# 04-ANDStatusLed.net
KiCad netlist of a schematic drawn in Altium Designer
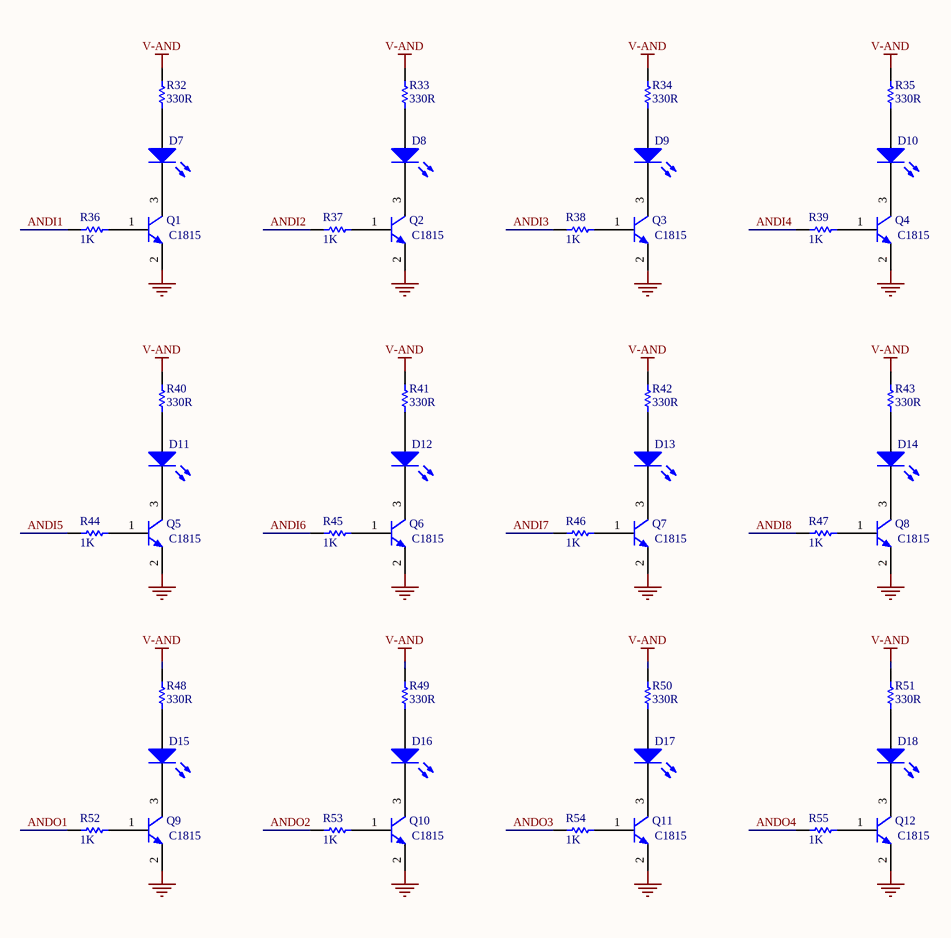
[diagram p0: 04-ANDStatusLed.SchDoc]

(export (version "E")
  (design (tool "Eeschema 10.0.6"))
  (components
    (comp (ref "D7")
      (value "LED")
      (footprint "LED-3528")
      (description "Typical RED, GREEN, YELLOW, AMBER GaAs LED")
      (fields (field (name "PUBLISHER") "Altium Limited"))
      (libsource (lib "Miscellaneous Devices") (part "LED2"))
    )
    (comp (ref "D8")
      (value "LED")
      (footprint "LED-3528")
      (description "Typical RED, GREEN, YELLOW, AMBER GaAs LED")
      (fields (field (name "PUBLISHER") "Altium Limited"))
      (libsource (lib "Miscellaneous Devices") (part "LED2"))
    )
    (comp (ref "D9")
      (value "LED")
      (footprint "LED-3528")
      (description "Typical RED, GREEN, YELLOW, AMBER GaAs LED")
      (fields (field (name "PUBLISHER") "Altium Limited"))
      (libsource (lib "Miscellaneous Devices") (part "LED2"))
    )
    (comp (ref "D10")
      (value "LED")
      (footprint "LED-3528")
      (description "Typical RED, GREEN, YELLOW, AMBER GaAs LED")
      (fields (field (name "PUBLISHER") "Altium Limited"))
      (libsource (lib "Miscellaneous Devices") (part "LED2"))
    )
    (comp (ref "D11")
      (value "LED")
      (footprint "LED-3528")
      (description "Typical RED, GREEN, YELLOW, AMBER GaAs LED")
      (fields (field (name "PUBLISHER") "Altium Limited"))
      (libsource (lib "Miscellaneous Devices") (part "LED2"))
    )
    (comp (ref "D12")
      (value "LED")
      (footprint "LED-3528")
      (description "Typical RED, GREEN, YELLOW, AMBER GaAs LED")
      (fields (field (name "PUBLISHER") "Altium Limited"))
      (libsource (lib "Miscellaneous Devices") (part "LED2"))
    )
    (comp (ref "D13")
      (value "LED")
      (footprint "LED-3528")
      (description "Typical RED, GREEN, YELLOW, AMBER GaAs LED")
      (fields (field (name "PUBLISHER") "Altium Limited"))
      (libsource (lib "Miscellaneous Devices") (part "LED2"))
    )
    (comp (ref "D14")
      (value "LED")
      (footprint "LED-3528")
      (description "Typical RED, GREEN, YELLOW, AMBER GaAs LED")
      (fields (field (name "PUBLISHER") "Altium Limited"))
      (libsource (lib "Miscellaneous Devices") (part "LED2"))
    )
    (comp (ref "D15")
      (value "LED")
      (footprint "LED-3528")
      (description "Typical RED, GREEN, YELLOW, AMBER GaAs LED")
      (fields (field (name "PUBLISHER") "Altium Limited"))
      (libsource (lib "Miscellaneous Devices") (part "LED2"))
    )
    (comp (ref "D16")
      (value "LED")
      (footprint "LED-3528")
      (description "Typical RED, GREEN, YELLOW, AMBER GaAs LED")
      (fields (field (name "PUBLISHER") "Altium Limited"))
      (libsource (lib "Miscellaneous Devices") (part "LED2"))
    )
    (comp (ref "D17")
      (value "LED")
      (footprint "LED-3528")
      (description "Typical RED, GREEN, YELLOW, AMBER GaAs LED")
      (fields (field (name "PUBLISHER") "Altium Limited"))
      (libsource (lib "Miscellaneous Devices") (part "LED2"))
    )
    (comp (ref "D18")
      (value "LED")
      (footprint "LED-3528")
      (description "Typical RED, GREEN, YELLOW, AMBER GaAs LED")
      (fields (field (name "PUBLISHER") "Altium Limited"))
      (libsource (lib "Miscellaneous Devices") (part "LED2"))
    )
    (comp (ref "Q1")
      (value "C1815")
      (footprint "SOT23-321")
      (description "NPN Bipolar Transistor")
      (fields (field (name "Comment") "C1815-SMD"))
      (libsource (lib "Miscellaneous Devices") (part "NPN"))
    )
    (comp (ref "Q2")
      (value "C1815")
      (footprint "SOT23-321")
      (description "NPN Bipolar Transistor")
      (fields (field (name "Comment") "C1815-SMD"))
      (libsource (lib "Miscellaneous Devices") (part "NPN"))
    )
    (comp (ref "Q3")
      (value "C1815")
      (footprint "SOT23-321")
      (description "NPN Bipolar Transistor")
      (fields (field (name "Comment") "C1815-SMD"))
      (libsource (lib "Miscellaneous Devices") (part "NPN"))
    )
    (comp (ref "Q4")
      (value "C1815")
      (footprint "SOT23-321")
      (description "NPN Bipolar Transistor")
      (fields (field (name "Comment") "C1815-SMD"))
      (libsource (lib "Miscellaneous Devices") (part "NPN"))
    )
    (comp (ref "Q5")
      (value "C1815")
      (footprint "SOT23-321")
      (description "NPN Bipolar Transistor")
      (fields (field (name "Comment") "C1815-SMD"))
      (libsource (lib "Miscellaneous Devices") (part "NPN"))
    )
    (comp (ref "Q6")
      (value "C1815")
      (footprint "SOT23-321")
      (description "NPN Bipolar Transistor")
      (fields (field (name "Comment") "C1815-SMD"))
      (libsource (lib "Miscellaneous Devices") (part "NPN"))
    )
    (comp (ref "Q7")
      (value "C1815")
      (footprint "SOT23-321")
      (description "NPN Bipolar Transistor")
      (fields (field (name "Comment") "C1815-SMD"))
      (libsource (lib "Miscellaneous Devices") (part "NPN"))
    )
    (comp (ref "Q8")
      (value "C1815")
      (footprint "SOT23-321")
      (description "NPN Bipolar Transistor")
      (fields (field (name "Comment") "C1815-SMD"))
      (libsource (lib "Miscellaneous Devices") (part "NPN"))
    )
    (comp (ref "Q9")
      (value "C1815")
      (footprint "SOT23-321")
      (description "NPN Bipolar Transistor")
      (fields (field (name "Comment") "C1815-SMD"))
      (libsource (lib "Miscellaneous Devices") (part "NPN"))
    )
    (comp (ref "Q10")
      (value "C1815")
      (footprint "SOT23-321")
      (description "NPN Bipolar Transistor")
      (fields (field (name "Comment") "C1815-SMD"))
      (libsource (lib "Miscellaneous Devices") (part "NPN"))
    )
    (comp (ref "Q11")
      (value "C1815")
      (footprint "SOT23-321")
      (description "NPN Bipolar Transistor")
      (fields (field (name "Comment") "C1815-SMD"))
      (libsource (lib "Miscellaneous Devices") (part "NPN"))
    )
    (comp (ref "Q12")
      (value "C1815")
      (footprint "SOT23-321")
      (description "NPN Bipolar Transistor")
      (fields (field (name "Comment") "C1815-SMD"))
      (libsource (lib "Miscellaneous Devices") (part "NPN"))
    )
    (comp (ref "R32")
      (value "330R")
      (footprint "R-0805")
      (description "Resistor")
      (fields (field (name "PUBLISHER") "Altium Limited"))
      (libsource (lib "Miscellaneous Devices") (part "Res1"))
    )
    (comp (ref "R33")
      (value "330R")
      (footprint "R-0805")
      (description "Resistor")
      (fields (field (name "PUBLISHER") "Altium Limited"))
      (libsource (lib "Miscellaneous Devices") (part "Res1"))
    )
    (comp (ref "R34")
      (value "330R")
      (footprint "R-0805")
      (description "Resistor")
      (fields (field (name "PUBLISHER") "Altium Limited"))
      (libsource (lib "Miscellaneous Devices") (part "Res1"))
    )
    (comp (ref "R35")
      (value "330R")
      (footprint "R-0805")
      (description "Resistor")
      (fields (field (name "PUBLISHER") "Altium Limited"))
      (libsource (lib "Miscellaneous Devices") (part "Res1"))
    )
    (comp (ref "R36")
      (value "1K")
      (footprint "R-0805")
      (description "Resistor")
      (fields (field (name "PUBLISHER") "Altium Limited"))
      (libsource (lib "Miscellaneous Devices") (part "Res1"))
    )
    (comp (ref "R37")
      (value "1K")
      (footprint "R-0805")
      (description "Resistor")
      (fields (field (name "PUBLISHER") "Altium Limited"))
      (libsource (lib "Miscellaneous Devices") (part "Res1"))
    )
    (comp (ref "R38")
      (value "1K")
      (footprint "R-0805")
      (description "Resistor")
      (fields (field (name "PUBLISHER") "Altium Limited"))
      (libsource (lib "Miscellaneous Devices") (part "Res1"))
    )
    (comp (ref "R39")
      (value "1K")
      (footprint "R-0805")
      (description "Resistor")
      (fields (field (name "PUBLISHER") "Altium Limited"))
      (libsource (lib "Miscellaneous Devices") (part "Res1"))
    )
    (comp (ref "R40")
      (value "330R")
      (footprint "R-0805")
      (description "Resistor")
      (fields (field (name "PUBLISHER") "Altium Limited"))
      (libsource (lib "Miscellaneous Devices") (part "Res1"))
    )
    (comp (ref "R41")
      (value "330R")
      (footprint "R-0805")
      (description "Resistor")
      (fields (field (name "PUBLISHER") "Altium Limited"))
      (libsource (lib "Miscellaneous Devices") (part "Res1"))
    )
    (comp (ref "R42")
      (value "330R")
      (footprint "R-0805")
      (description "Resistor")
      (fields (field (name "PUBLISHER") "Altium Limited"))
      (libsource (lib "Miscellaneous Devices") (part "Res1"))
    )
    (comp (ref "R43")
      (value "330R")
      (footprint "R-0805")
      (description "Resistor")
      (fields (field (name "PUBLISHER") "Altium Limited"))
      (libsource (lib "Miscellaneous Devices") (part "Res1"))
    )
    (comp (ref "R44")
      (value "1K")
      (footprint "R-0805")
      (description "Resistor")
      (fields (field (name "PUBLISHER") "Altium Limited"))
      (libsource (lib "Miscellaneous Devices") (part "Res1"))
    )
    (comp (ref "R45")
      (value "1K")
      (footprint "R-0805")
      (description "Resistor")
      (fields (field (name "PUBLISHER") "Altium Limited"))
      (libsource (lib "Miscellaneous Devices") (part "Res1"))
    )
    (comp (ref "R46")
      (value "1K")
      (footprint "R-0805")
      (description "Resistor")
      (fields (field (name "PUBLISHER") "Altium Limited"))
      (libsource (lib "Miscellaneous Devices") (part "Res1"))
    )
    (comp (ref "R47")
      (value "1K")
      (footprint "R-0805")
      (description "Resistor")
      (fields (field (name "PUBLISHER") "Altium Limited"))
      (libsource (lib "Miscellaneous Devices") (part "Res1"))
    )
    (comp (ref "R48")
      (value "330R")
      (footprint "R-0805")
      (description "Resistor")
      (fields (field (name "PUBLISHER") "Altium Limited"))
      (libsource (lib "Miscellaneous Devices") (part "Res1"))
    )
    (comp (ref "R49")
      (value "330R")
      (footprint "R-0805")
      (description "Resistor")
      (fields (field (name "PUBLISHER") "Altium Limited"))
      (libsource (lib "Miscellaneous Devices") (part "Res1"))
    )
    (comp (ref "R50")
      (value "330R")
      (footprint "R-0805")
      (description "Resistor")
      (fields (field (name "PUBLISHER") "Altium Limited"))
      (libsource (lib "Miscellaneous Devices") (part "Res1"))
    )
    (comp (ref "R51")
      (value "330R")
      (footprint "R-0805")
      (description "Resistor")
      (fields (field (name "PUBLISHER") "Altium Limited"))
      (libsource (lib "Miscellaneous Devices") (part "Res1"))
    )
    (comp (ref "R52")
      (value "1K")
      (footprint "R-0805")
      (description "Resistor")
      (fields (field (name "PUBLISHER") "Altium Limited"))
      (libsource (lib "Miscellaneous Devices") (part "Res1"))
    )
    (comp (ref "R53")
      (value "1K")
      (footprint "R-0805")
      (description "Resistor")
      (fields (field (name "PUBLISHER") "Altium Limited"))
      (libsource (lib "Miscellaneous Devices") (part "Res1"))
    )
    (comp (ref "R54")
      (value "1K")
      (footprint "R-0805")
      (description "Resistor")
      (fields (field (name "PUBLISHER") "Altium Limited"))
      (libsource (lib "Miscellaneous Devices") (part "Res1"))
    )
    (comp (ref "R55")
      (value "1K")
      (footprint "R-0805")
      (description "Resistor")
      (fields (field (name "PUBLISHER") "Altium Limited"))
      (libsource (lib "Miscellaneous Devices") (part "Res1"))
    )
  )
  (nets
    (net (code "1") (name "/ANDI1") (class "Default")
      (node (ref "R36") (pin "2") (pinfunction "2_2") (pintype "passive"))
    )
    (net (code "2") (name "/ANDI2") (class "Default")
      (node (ref "R37") (pin "2") (pinfunction "2_2") (pintype "passive"))
    )
    (net (code "3") (name "/ANDI3") (class "Default")
      (node (ref "R38") (pin "2") (pinfunction "2_2") (pintype "passive"))
    )
    (net (code "4") (name "/ANDI4") (class "Default")
      (node (ref "R39") (pin "2") (pinfunction "2_2") (pintype "passive"))
    )
    (net (code "5") (name "/ANDI5") (class "Default")
      (node (ref "R44") (pin "2") (pinfunction "2_2") (pintype "passive"))
    )
    (net (code "6") (name "/ANDI6") (class "Default")
      (node (ref "R45") (pin "2") (pinfunction "2_2") (pintype "passive"))
    )
    (net (code "7") (name "/ANDI7") (class "Default")
      (node (ref "R46") (pin "2") (pinfunction "2_2") (pintype "passive"))
    )
    (net (code "8") (name "/ANDI8") (class "Default")
      (node (ref "R47") (pin "2") (pinfunction "2_2") (pintype "passive"))
    )
    (net (code "9") (name "/ANDO1") (class "Default")
      (node (ref "R52") (pin "2") (pinfunction "2_2") (pintype "passive"))
    )
    (net (code "10") (name "/ANDO2") (class "Default")
      (node (ref "R53") (pin "2") (pinfunction "2_2") (pintype "passive"))
    )
    (net (code "11") (name "/ANDO3") (class "Default")
      (node (ref "R54") (pin "2") (pinfunction "2_2") (pintype "passive"))
    )
    (net (code "12") (name "/ANDO4") (class "Default")
      (node (ref "R55") (pin "2") (pinfunction "2_2") (pintype "passive"))
    )
    (net (code "13") (name "GND") (class "Default")
      (node (ref "Q1") (pin "2") (pinfunction "E_2") (pintype "passive"))
      (node (ref "Q10") (pin "2") (pinfunction "E_2") (pintype "passive"))
      (node (ref "Q11") (pin "2") (pinfunction "E_2") (pintype "passive"))
      (node (ref "Q12") (pin "2") (pinfunction "E_2") (pintype "passive"))
      (node (ref "Q2") (pin "2") (pinfunction "E_2") (pintype "passive"))
      (node (ref "Q3") (pin "2") (pinfunction "E_2") (pintype "passive"))
      (node (ref "Q4") (pin "2") (pinfunction "E_2") (pintype "passive"))
      (node (ref "Q5") (pin "2") (pinfunction "E_2") (pintype "passive"))
      (node (ref "Q6") (pin "2") (pinfunction "E_2") (pintype "passive"))
      (node (ref "Q7") (pin "2") (pinfunction "E_2") (pintype "passive"))
      (node (ref "Q8") (pin "2") (pinfunction "E_2") (pintype "passive"))
      (node (ref "Q9") (pin "2") (pinfunction "E_2") (pintype "passive"))
    )
    (net (code "14") (name "Net-(D7-A)") (class "Default")
      (node (ref "D7") (pin "1") (pinfunction "A_1") (pintype "passive"))
      (node (ref "R32") (pin "1") (pinfunction "1_1") (pintype "passive"))
    )
    (net (code "15") (name "Net-(D7-K)") (class "Default")
      (node (ref "D7") (pin "2") (pinfunction "K_2") (pintype "passive"))
      (node (ref "Q1") (pin "3") (pinfunction "C_3") (pintype "passive"))
    )
    (net (code "16") (name "Net-(D8-A)") (class "Default")
      (node (ref "D8") (pin "1") (pinfunction "A_1") (pintype "passive"))
      (node (ref "R33") (pin "1") (pinfunction "1_1") (pintype "passive"))
    )
    (net (code "17") (name "Net-(D8-K)") (class "Default")
      (node (ref "D8") (pin "2") (pinfunction "K_2") (pintype "passive"))
      (node (ref "Q2") (pin "3") (pinfunction "C_3") (pintype "passive"))
    )
    (net (code "18") (name "Net-(D9-A)") (class "Default")
      (node (ref "D9") (pin "1") (pinfunction "A_1") (pintype "passive"))
      (node (ref "R34") (pin "1") (pinfunction "1_1") (pintype "passive"))
    )
    (net (code "19") (name "Net-(D9-K)") (class "Default")
      (node (ref "D9") (pin "2") (pinfunction "K_2") (pintype "passive"))
      (node (ref "Q3") (pin "3") (pinfunction "C_3") (pintype "passive"))
    )
    (net (code "20") (name "Net-(D10-A)") (class "Default")
      (node (ref "D10") (pin "1") (pinfunction "A_1") (pintype "passive"))
      (node (ref "R35") (pin "1") (pinfunction "1_1") (pintype "passive"))
    )
    (net (code "21") (name "Net-(D10-K)") (class "Default")
      (node (ref "D10") (pin "2") (pinfunction "K_2") (pintype "passive"))
      (node (ref "Q4") (pin "3") (pinfunction "C_3") (pintype "passive"))
    )
    (net (code "22") (name "Net-(D11-A)") (class "Default")
      (node (ref "D11") (pin "1") (pinfunction "A_1") (pintype "passive"))
      (node (ref "R40") (pin "1") (pinfunction "1_1") (pintype "passive"))
    )
    (net (code "23") (name "Net-(D11-K)") (class "Default")
      (node (ref "D11") (pin "2") (pinfunction "K_2") (pintype "passive"))
      (node (ref "Q5") (pin "3") (pinfunction "C_3") (pintype "passive"))
    )
    (net (code "24") (name "Net-(D12-A)") (class "Default")
      (node (ref "D12") (pin "1") (pinfunction "A_1") (pintype "passive"))
      (node (ref "R41") (pin "1") (pinfunction "1_1") (pintype "passive"))
    )
    (net (code "25") (name "Net-(D12-K)") (class "Default")
      (node (ref "D12") (pin "2") (pinfunction "K_2") (pintype "passive"))
      (node (ref "Q6") (pin "3") (pinfunction "C_3") (pintype "passive"))
    )
    (net (code "26") (name "Net-(D13-A)") (class "Default")
      (node (ref "D13") (pin "1") (pinfunction "A_1") (pintype "passive"))
      (node (ref "R42") (pin "1") (pinfunction "1_1") (pintype "passive"))
    )
    (net (code "27") (name "Net-(D13-K)") (class "Default")
      (node (ref "D13") (pin "2") (pinfunction "K_2") (pintype "passive"))
      (node (ref "Q7") (pin "3") (pinfunction "C_3") (pintype "passive"))
    )
    (net (code "28") (name "Net-(D14-A)") (class "Default")
      (node (ref "D14") (pin "1") (pinfunction "A_1") (pintype "passive"))
      (node (ref "R43") (pin "1") (pinfunction "1_1") (pintype "passive"))
    )
    (net (code "29") (name "Net-(D14-K)") (class "Default")
      (node (ref "D14") (pin "2") (pinfunction "K_2") (pintype "passive"))
      (node (ref "Q8") (pin "3") (pinfunction "C_3") (pintype "passive"))
    )
    (net (code "30") (name "Net-(D15-A)") (class "Default")
      (node (ref "D15") (pin "1") (pinfunction "A_1") (pintype "passive"))
      (node (ref "R48") (pin "1") (pinfunction "1_1") (pintype "passive"))
    )
    (net (code "31") (name "Net-(D15-K)") (class "Default")
      (node (ref "D15") (pin "2") (pinfunction "K_2") (pintype "passive"))
      (node (ref "Q9") (pin "3") (pinfunction "C_3") (pintype "passive"))
    )
    (net (code "32") (name "Net-(D16-A)") (class "Default")
      (node (ref "D16") (pin "1") (pinfunction "A_1") (pintype "passive"))
      (node (ref "R49") (pin "1") (pinfunction "1_1") (pintype "passive"))
    )
    (net (code "33") (name "Net-(D16-K)") (class "Default")
      (node (ref "D16") (pin "2") (pinfunction "K_2") (pintype "passive"))
      (node (ref "Q10") (pin "3") (pinfunction "C_3") (pintype "passive"))
    )
    (net (code "34") (name "Net-(D17-A)") (class "Default")
      (node (ref "D17") (pin "1") (pinfunction "A_1") (pintype "passive"))
      (node (ref "R50") (pin "1") (pinfunction "1_1") (pintype "passive"))
    )
    (net (code "35") (name "Net-(D17-K)") (class "Default")
      (node (ref "D17") (pin "2") (pinfunction "K_2") (pintype "passive"))
      (node (ref "Q11") (pin "3") (pinfunction "C_3") (pintype "passive"))
    )
    (net (code "36") (name "Net-(D18-A)") (class "Default")
      (node (ref "D18") (pin "1") (pinfunction "A_1") (pintype "passive"))
      (node (ref "R51") (pin "1") (pinfunction "1_1") (pintype "passive"))
    )
    (net (code "37") (name "Net-(D18-K)") (class "Default")
      (node (ref "D18") (pin "2") (pinfunction "K_2") (pintype "passive"))
      (node (ref "Q12") (pin "3") (pinfunction "C_3") (pintype "passive"))
    )
    (net (code "38") (name "Net-(Q1-B)") (class "Default")
      (node (ref "Q1") (pin "1") (pinfunction "B_1") (pintype "passive"))
      (node (ref "R36") (pin "1") (pinfunction "1_1") (pintype "passive"))
    )
    (net (code "39") (name "Net-(Q2-B)") (class "Default")
      (node (ref "Q2") (pin "1") (pinfunction "B_1") (pintype "passive"))
      (node (ref "R37") (pin "1") (pinfunction "1_1") (pintype "passive"))
    )
    (net (code "40") (name "Net-(Q3-B)") (class "Default")
      (node (ref "Q3") (pin "1") (pinfunction "B_1") (pintype "passive"))
      (node (ref "R38") (pin "1") (pinfunction "1_1") (pintype "passive"))
    )
    (net (code "41") (name "Net-(Q4-B)") (class "Default")
      (node (ref "Q4") (pin "1") (pinfunction "B_1") (pintype "passive"))
      (node (ref "R39") (pin "1") (pinfunction "1_1") (pintype "passive"))
    )
    (net (code "42") (name "Net-(Q5-B)") (class "Default")
      (node (ref "Q5") (pin "1") (pinfunction "B_1") (pintype "passive"))
      (node (ref "R44") (pin "1") (pinfunction "1_1") (pintype "passive"))
    )
    (net (code "43") (name "Net-(Q6-B)") (class "Default")
      (node (ref "Q6") (pin "1") (pinfunction "B_1") (pintype "passive"))
      (node (ref "R45") (pin "1") (pinfunction "1_1") (pintype "passive"))
    )
    (net (code "44") (name "Net-(Q7-B)") (class "Default")
      (node (ref "Q7") (pin "1") (pinfunction "B_1") (pintype "passive"))
      (node (ref "R46") (pin "1") (pinfunction "1_1") (pintype "passive"))
    )
    (net (code "45") (name "Net-(Q8-B)") (class "Default")
      (node (ref "Q8") (pin "1") (pinfunction "B_1") (pintype "passive"))
      (node (ref "R47") (pin "1") (pinfunction "1_1") (pintype "passive"))
    )
    (net (code "46") (name "Net-(Q9-B)") (class "Default")
      (node (ref "Q9") (pin "1") (pinfunction "B_1") (pintype "passive"))
      (node (ref "R52") (pin "1") (pinfunction "1_1") (pintype "passive"))
    )
    (net (code "47") (name "Net-(Q10-B)") (class "Default")
      (node (ref "Q10") (pin "1") (pinfunction "B_1") (pintype "passive"))
      (node (ref "R53") (pin "1") (pinfunction "1_1") (pintype "passive"))
    )
    (net (code "48") (name "Net-(Q11-B)") (class "Default")
      (node (ref "Q11") (pin "1") (pinfunction "B_1") (pintype "passive"))
      (node (ref "R54") (pin "1") (pinfunction "1_1") (pintype "passive"))
    )
    (net (code "49") (name "Net-(Q12-B)") (class "Default")
      (node (ref "Q12") (pin "1") (pinfunction "B_1") (pintype "passive"))
      (node (ref "R55") (pin "1") (pinfunction "1_1") (pintype "passive"))
    )
    (net (code "50") (name "V-AND") (class "Default")
      (node (ref "R32") (pin "2") (pinfunction "2_2") (pintype "passive"))
      (node (ref "R33") (pin "2") (pinfunction "2_2") (pintype "passive"))
      (node (ref "R34") (pin "2") (pinfunction "2_2") (pintype "passive"))
      (node (ref "R35") (pin "2") (pinfunction "2_2") (pintype "passive"))
      (node (ref "R40") (pin "2") (pinfunction "2_2") (pintype "passive"))
      (node (ref "R41") (pin "2") (pinfunction "2_2") (pintype "passive"))
      (node (ref "R42") (pin "2") (pinfunction "2_2") (pintype "passive"))
      (node (ref "R43") (pin "2") (pinfunction "2_2") (pintype "passive"))
      (node (ref "R48") (pin "2") (pinfunction "2_2") (pintype "passive"))
      (node (ref "R49") (pin "2") (pinfunction "2_2") (pintype "passive"))
      (node (ref "R50") (pin "2") (pinfunction "2_2") (pintype "passive"))
      (node (ref "R51") (pin "2") (pinfunction "2_2") (pintype "passive"))
    )
  )
)
